# LDOs.net
KiCad netlist of a schematic drawn in Altium Designer
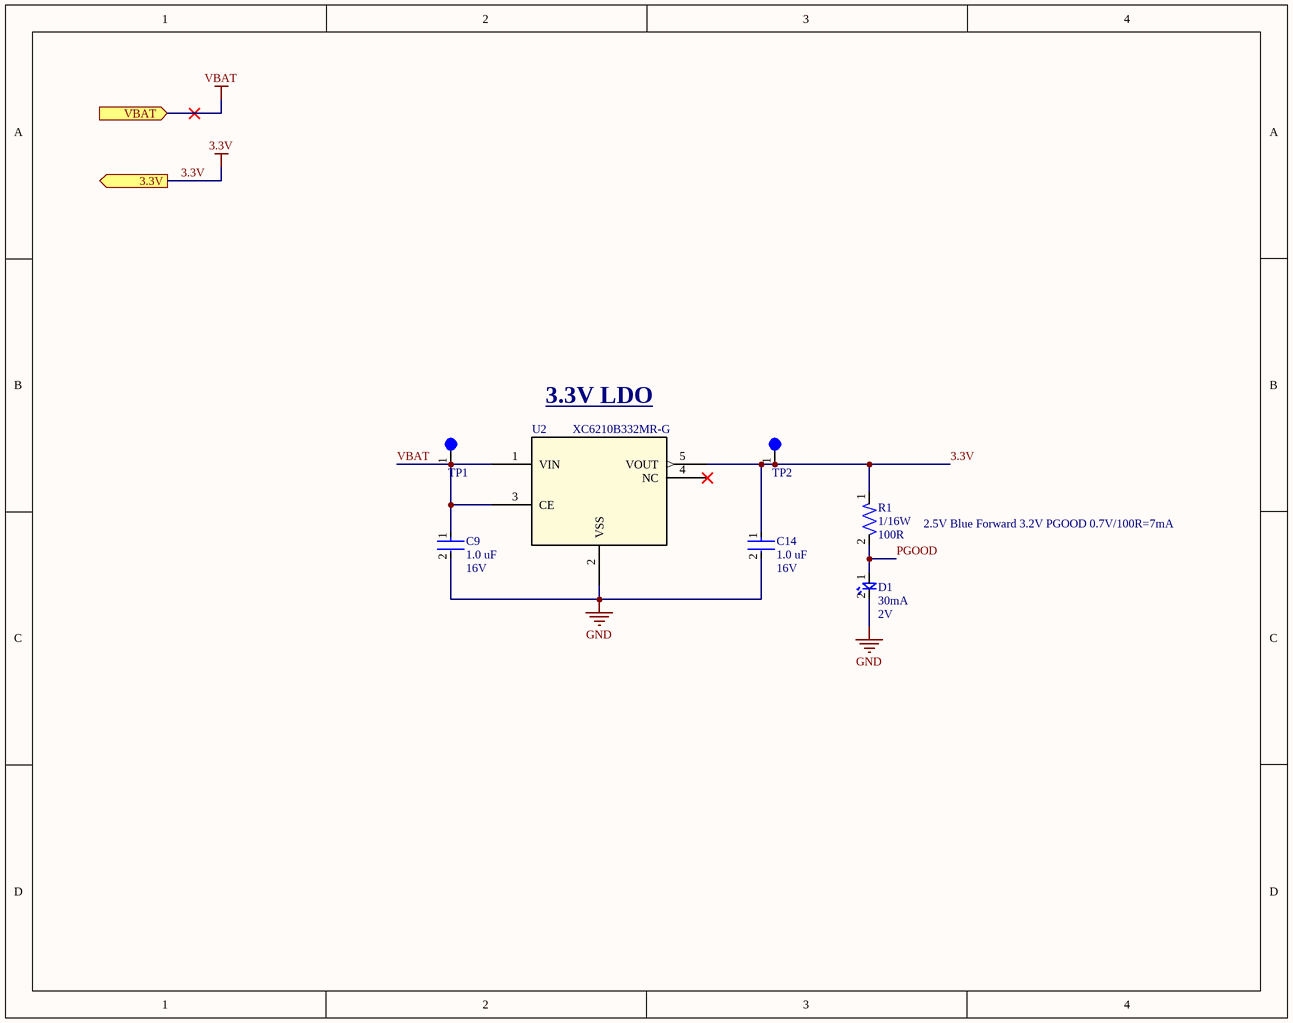
[diagram p0: LDOs.SchDoc]

(export (version "E")
  (design (tool "Eeschema 10.0.6"))
  (components
    (comp (ref "C9")
      (value "CC0603KRX7R7BB105")
      (footprint "CAP-0603")
      (description "CAP CER 1UF 16V X7R 0603")
      (fields (field (name "CAPACITANCE") "1.0 uF") (field (name "VOLTAGE") "16V"))
      (libsource (lib "JLC_25") (part "CAP-1U-0002"))
    )
    (comp (ref "C14")
      (value "CC0603KRX7R7BB105")
      (footprint "CAP-0603")
      (description "CAP CER 1UF 16V X7R 0603")
      (fields (field (name "CAPACITANCE") "1.0 uF") (field (name "VOLTAGE") "16V"))
      (libsource (lib "JLC_25") (part "CAP-1U-0002"))
    )
    (comp (ref "D1")
      (value "BL-HKC36G-AV-TRB")
      (footprint "LED-0603")
      (description "LED YELLOW CLEAR 0603 SMD")
      (fields (field (name "FORWARD CURRENT") "30mA") (field (name "FORWARD VOLTAGE") "2V"))
      (libsource (lib "JLC_25") (part "LED-0001"))
    )
    (comp (ref "R1")
      (value "RC0402FR-07100RL")
      (footprint "RES-0402")
      (description "RES 100 OHM 1% 1/16W 0402")
      (fields
        (field (name "TOLERANCE") "1%")
        (field (name "POWER") "1/16W")
        (field (name "RESISTANCE") "100R")
      )
      (libsource (lib "JLC_25") (part "RES-100-0001"))
    )
    (comp (ref "TP1")
      (value "5003")
      (footprint "TEST-POINT-0001")
      (description "Oranange PC Test Point, Miniature Phoisphor Bronze Silver Plating Through Hole Mounting Type")
      (libsource (lib "JLC_25") (part "TEST-POINT-0001"))
    )
    (comp (ref "TP2")
      (value "5003")
      (footprint "TEST-POINT-0001")
      (description "Oranange PC Test Point, Miniature Phoisphor Bronze Silver Plating Through Hole Mounting Type")
      (libsource (lib "JLC_25") (part "TEST-POINT-0001"))
    )
    (comp (ref "U2")
      (value "XC6210B332MR-G")
      (footprint "SOT-25_TOR")
      (description "Linear Voltage Regulator IC Positive Fixed 1 Output 700mA SOT-25-5")
      (libsource (lib "eecs373Lib") (part "LDO-3.3V_1"))
    )
  )
  (nets
    (net (code "1") (name "/PGOOD") (class "Default")
      (node (ref "D1") (pin "1") (pinfunction "1_1") (pintype "passive"))
      (node (ref "R1") (pin "2") (pinfunction "2_2") (pintype "passive"))
    )
    (net (code "2") (name "3.3V") (class "Default")
      (node (ref "C14") (pin "1") (pinfunction "1_1") (pintype "passive"))
      (node (ref "R1") (pin "1") (pinfunction "1_1") (pintype "passive"))
      (node (ref "TP2") (pin "1") (pinfunction "0_1") (pintype "passive"))
      (node (ref "U2") (pin "5") (pinfunction "VOUT_5") (pintype "output"))
    )
    (net (code "3") (name "GND") (class "Default")
      (node (ref "C14") (pin "2") (pinfunction "2_2") (pintype "passive"))
      (node (ref "C9") (pin "2") (pinfunction "2_2") (pintype "passive"))
      (node (ref "D1") (pin "2") (pinfunction "2_2") (pintype "passive"))
      (node (ref "U2") (pin "2") (pinfunction "VSS_2") (pintype "power_in"))
    )
    (net (code "4") (name "VBAT") (class "Default")
      (node (ref "C9") (pin "1") (pinfunction "1_1") (pintype "passive"))
      (node (ref "TP1") (pin "1") (pinfunction "0_1") (pintype "passive"))
      (node (ref "U2") (pin "1") (pinfunction "VIN_1") (pintype "power_in"))
      (node (ref "U2") (pin "3") (pinfunction "CE_3") (pintype "passive"))
    )
    (net (code "5") (name "unconnected-(U2-NC-Pad4)") (class "Default")
      (node (ref "U2") (pin "4") (pinfunction "NC_4") (pintype "passive+no_connect"))
    )
  )
)
